# Bipolar_Matrix_Mixer_4x2_v5.net
KiCad netlist of a schematic drawn in EAGLE
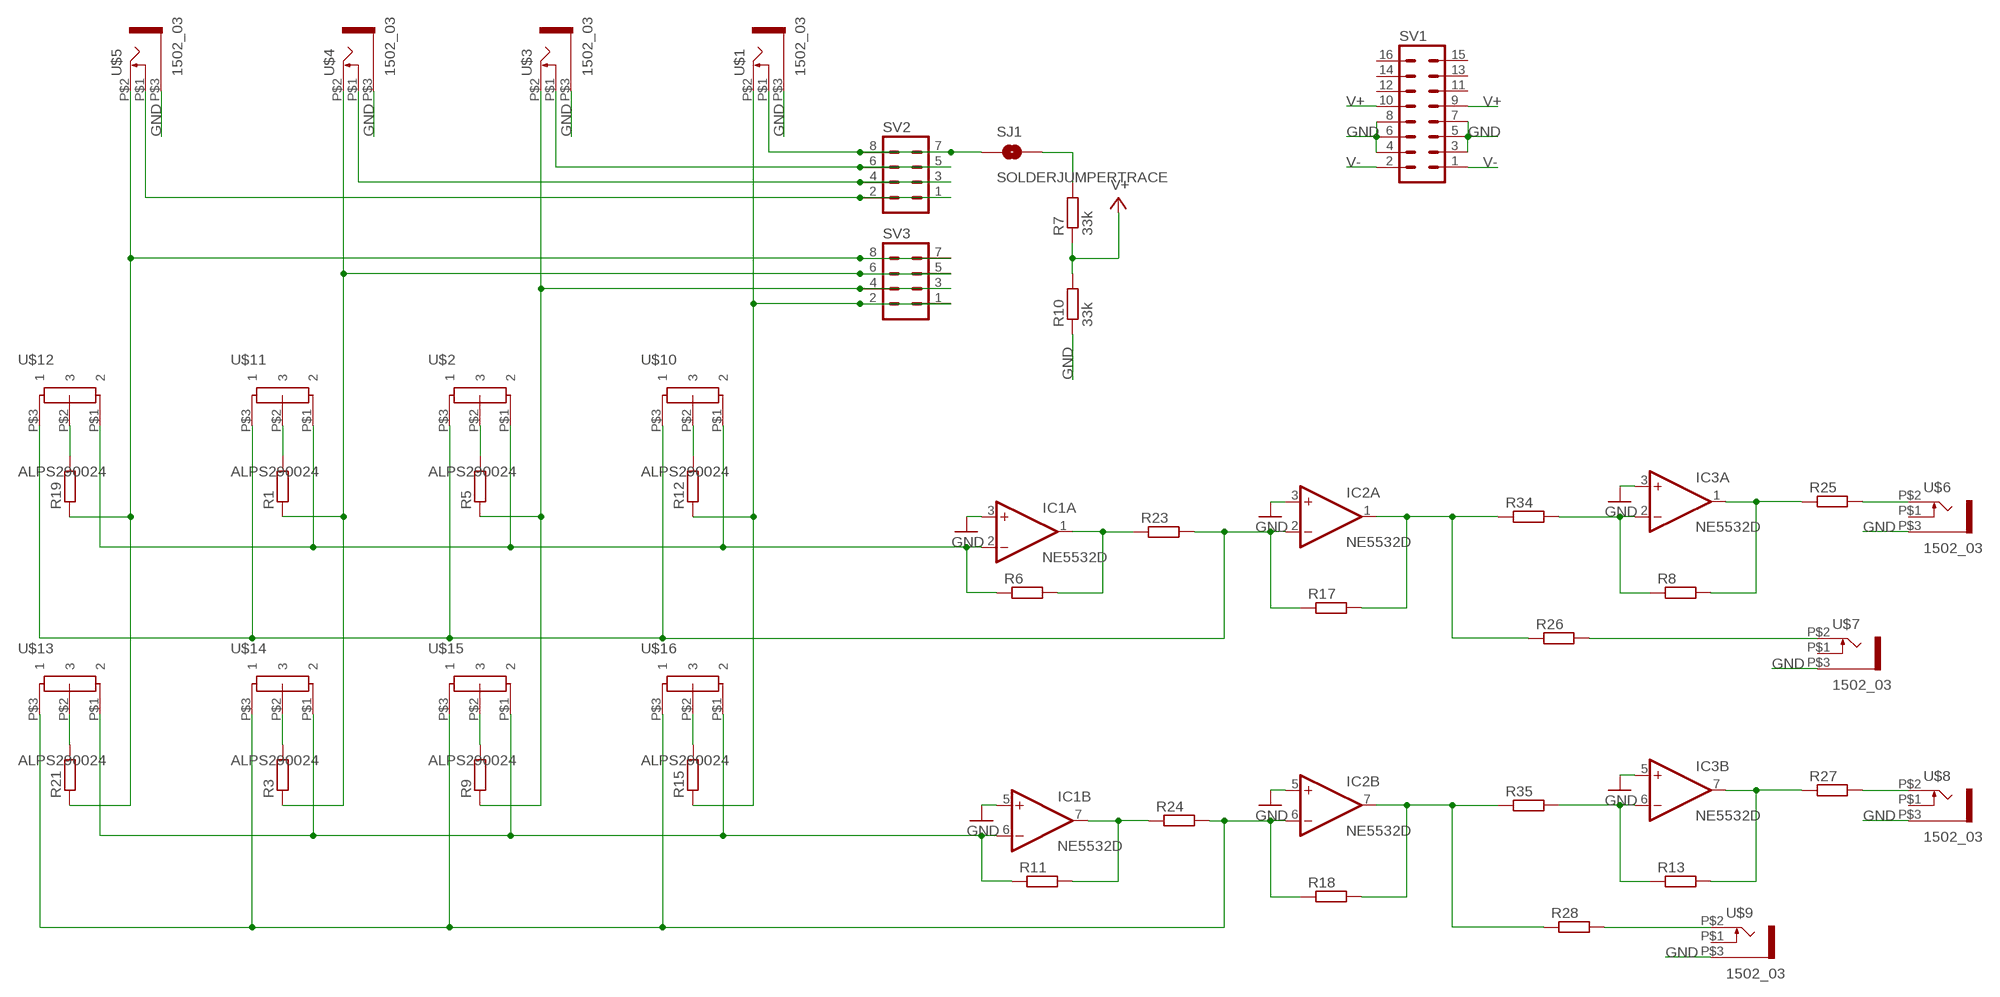
[diagram p0: schematic, sheet 1]

(export (version "E")
  (design (tool "Eeschema 10.0.6"))
  (components
    (comp (ref "IC1")
      (value "NE5532D")
      (footprint "eagle-import:SO08")
      (libsource (lib "eagle-import") (part "NE5532D"))
    )
    (comp (ref "IC2")
      (value "NE5532D")
      (footprint "eagle-import:SO08")
      (libsource (lib "eagle-import") (part "NE5532D"))
    )
    (comp (ref "IC3")
      (value "NE5532D")
      (footprint "eagle-import:SO08")
      (libsource (lib "eagle-import") (part "NE5532D"))
    )
    (comp (ref "R1")
      (value "R-EU_R0603")
      (footprint "eagle-import:R0603")
      (libsource (lib "eagle-import") (part "R-EU_R0603"))
    )
    (comp (ref "R3")
      (value "R-EU_R0603")
      (footprint "eagle-import:R0603")
      (libsource (lib "eagle-import") (part "R-EU_R0603"))
    )
    (comp (ref "R5")
      (value "R-EU_R0603")
      (footprint "eagle-import:R0603")
      (libsource (lib "eagle-import") (part "R-EU_R0603"))
    )
    (comp (ref "R6")
      (value "R-EU_R0603")
      (footprint "eagle-import:R0603")
      (libsource (lib "eagle-import") (part "R-EU_R0603"))
    )
    (comp (ref "R7")
      (value "33k")
      (footprint "eagle-import:R0603")
      (libsource (lib "eagle-import") (part "R-EU_R0603"))
    )
    (comp (ref "R8")
      (value "R-EU_R0603")
      (footprint "eagle-import:R0603")
      (libsource (lib "eagle-import") (part "R-EU_R0603"))
    )
    (comp (ref "R9")
      (value "R-EU_R0603")
      (footprint "eagle-import:R0603")
      (libsource (lib "eagle-import") (part "R-EU_R0603"))
    )
    (comp (ref "R10")
      (value "33k")
      (footprint "eagle-import:R0603")
      (libsource (lib "eagle-import") (part "R-EU_R0603"))
    )
    (comp (ref "R11")
      (value "R-EU_R0603")
      (footprint "eagle-import:R0603")
      (libsource (lib "eagle-import") (part "R-EU_R0603"))
    )
    (comp (ref "R12")
      (value "R-EU_R0603")
      (footprint "eagle-import:R0603")
      (libsource (lib "eagle-import") (part "R-EU_R0603"))
    )
    (comp (ref "R13")
      (value "R-EU_R0603")
      (footprint "eagle-import:R0603")
      (libsource (lib "eagle-import") (part "R-EU_R0603"))
    )
    (comp (ref "R15")
      (value "R-EU_R0603")
      (footprint "eagle-import:R0603")
      (libsource (lib "eagle-import") (part "R-EU_R0603"))
    )
    (comp (ref "R17")
      (value "R-EU_R0603")
      (footprint "eagle-import:R0603")
      (libsource (lib "eagle-import") (part "R-EU_R0603"))
    )
    (comp (ref "R18")
      (value "R-EU_R0603")
      (footprint "eagle-import:R0603")
      (libsource (lib "eagle-import") (part "R-EU_R0603"))
    )
    (comp (ref "R19")
      (value "R-EU_R0603")
      (footprint "eagle-import:R0603")
      (libsource (lib "eagle-import") (part "R-EU_R0603"))
    )
    (comp (ref "R21")
      (value "R-EU_R0603")
      (footprint "eagle-import:R0603")
      (libsource (lib "eagle-import") (part "R-EU_R0603"))
    )
    (comp (ref "R23")
      (value "R-EU_R0603")
      (footprint "eagle-import:R0603")
      (libsource (lib "eagle-import") (part "R-EU_R0603"))
    )
    (comp (ref "R24")
      (value "R-EU_R0603")
      (footprint "eagle-import:R0603")
      (libsource (lib "eagle-import") (part "R-EU_R0603"))
    )
    (comp (ref "R25")
      (value "R-EU_R0603")
      (footprint "eagle-import:R0603")
      (libsource (lib "eagle-import") (part "R-EU_R0603"))
    )
    (comp (ref "R26")
      (value "R-EU_R0603")
      (footprint "eagle-import:R0603")
      (libsource (lib "eagle-import") (part "R-EU_R0603"))
    )
    (comp (ref "R27")
      (value "R-EU_R0603")
      (footprint "eagle-import:R0603")
      (libsource (lib "eagle-import") (part "R-EU_R0603"))
    )
    (comp (ref "R28")
      (value "R-EU_R0603")
      (footprint "eagle-import:R0603")
      (libsource (lib "eagle-import") (part "R-EU_R0603"))
    )
    (comp (ref "R34")
      (value "R-EU_R0603")
      (footprint "eagle-import:R0603")
      (libsource (lib "eagle-import") (part "R-EU_R0603"))
    )
    (comp (ref "R35")
      (value "R-EU_R0603")
      (footprint "eagle-import:R0603")
      (libsource (lib "eagle-import") (part "R-EU_R0603"))
    )
    (comp (ref "SJ1")
      (value "SOLDERJUMPERTRACE")
      (footprint "eagle-import:SJ_2S-TRACE")
      (libsource (lib "eagle-import") (part "SOLDERJUMPERTRACE"))
    )
    (comp (ref "SV1")
      (value "MA08-2")
      (footprint "eagle-import:MA08-2")
      (libsource (lib "eagle-import") (part "MA08-2"))
    )
    (comp (ref "SV2")
      (value "MA04-2")
      (footprint "eagle-import:MA04-2")
      (libsource (lib "eagle-import") (part "MA04-2"))
    )
    (comp (ref "SV3")
      (value "MA04-2")
      (footprint "eagle-import:MA04-2")
      (libsource (lib "eagle-import") (part "MA04-2"))
    )
    (comp (ref "U$1")
      (value "1502_03")
      (footprint "eagle-import:1502_03")
      (libsource (lib "eagle-import") (part "1502_03"))
    )
    (comp (ref "U$2")
      (value "ALPS290024")
      (footprint "eagle-import:POT")
      (libsource (lib "eagle-import") (part "ALPS290024"))
    )
    (comp (ref "U$3")
      (value "1502_03")
      (footprint "eagle-import:1502_03")
      (libsource (lib "eagle-import") (part "1502_03"))
    )
    (comp (ref "U$4")
      (value "1502_03")
      (footprint "eagle-import:1502_03")
      (libsource (lib "eagle-import") (part "1502_03"))
    )
    (comp (ref "U$5")
      (value "1502_03")
      (footprint "eagle-import:1502_03")
      (libsource (lib "eagle-import") (part "1502_03"))
    )
    (comp (ref "U$6")
      (value "1502_03")
      (footprint "eagle-import:1502_03")
      (libsource (lib "eagle-import") (part "1502_03"))
    )
    (comp (ref "U$7")
      (value "1502_03")
      (footprint "eagle-import:1502_03")
      (libsource (lib "eagle-import") (part "1502_03"))
    )
    (comp (ref "U$8")
      (value "1502_03")
      (footprint "eagle-import:1502_03")
      (libsource (lib "eagle-import") (part "1502_03"))
    )
    (comp (ref "U$9")
      (value "1502_03")
      (footprint "eagle-import:1502_03")
      (libsource (lib "eagle-import") (part "1502_03"))
    )
    (comp (ref "U$10")
      (value "ALPS290024")
      (footprint "eagle-import:POT")
      (libsource (lib "eagle-import") (part "ALPS290024"))
    )
    (comp (ref "U$11")
      (value "ALPS290024")
      (footprint "eagle-import:POT")
      (libsource (lib "eagle-import") (part "ALPS290024"))
    )
    (comp (ref "U$12")
      (value "ALPS290024")
      (footprint "eagle-import:POT")
      (libsource (lib "eagle-import") (part "ALPS290024"))
    )
    (comp (ref "U$13")
      (value "ALPS290024")
      (footprint "eagle-import:POT")
      (libsource (lib "eagle-import") (part "ALPS290024"))
    )
    (comp (ref "U$14")
      (value "ALPS290024")
      (footprint "eagle-import:POT")
      (libsource (lib "eagle-import") (part "ALPS290024"))
    )
    (comp (ref "U$15")
      (value "ALPS290024")
      (footprint "eagle-import:POT")
      (libsource (lib "eagle-import") (part "ALPS290024"))
    )
    (comp (ref "U$16")
      (value "ALPS290024")
      (footprint "eagle-import:POT")
      (libsource (lib "eagle-import") (part "ALPS290024"))
    )
  )
  (nets
    (net (code "1") (name "/V-") (class "Default")
      (node (ref "SV1") (pin "1") (pinfunction "1_1") (pintype "passive"))
      (node (ref "SV1") (pin "2") (pinfunction "2_2") (pintype "passive"))
    )
    (net (code "2") (name "GND") (class "Default")
      (node (ref "IC1") (pin "3") (pinfunction "+IN_3") (pintype "input"))
      (node (ref "IC1") (pin "5") (pinfunction "+IN_5") (pintype "input"))
      (node (ref "IC2") (pin "3") (pinfunction "+IN_3") (pintype "input"))
      (node (ref "IC2") (pin "5") (pinfunction "+IN_5") (pintype "input"))
      (node (ref "IC3") (pin "3") (pinfunction "+IN_3") (pintype "input"))
      (node (ref "IC3") (pin "5") (pinfunction "+IN_5") (pintype "input"))
      (node (ref "R10") (pin "1") (pinfunction "1_1") (pintype "passive"))
      (node (ref "SV1") (pin "3") (pinfunction "3_3") (pintype "passive"))
      (node (ref "SV1") (pin "4") (pinfunction "4_4") (pintype "passive"))
      (node (ref "SV1") (pin "5") (pinfunction "5_5") (pintype "passive"))
      (node (ref "SV1") (pin "6") (pinfunction "6_6") (pintype "passive"))
      (node (ref "SV1") (pin "7") (pinfunction "7_7") (pintype "passive"))
      (node (ref "SV1") (pin "8") (pinfunction "8_8") (pintype "passive"))
      (node (ref "U$1") (pin "P$3") (pinfunction "5_P$3") (pintype "passive"))
      (node (ref "U$3") (pin "P$3") (pinfunction "5_P$3") (pintype "passive"))
      (node (ref "U$4") (pin "P$3") (pinfunction "5_P$3") (pintype "passive"))
      (node (ref "U$5") (pin "P$3") (pinfunction "5_P$3") (pintype "passive"))
      (node (ref "U$6") (pin "P$3") (pinfunction "5_P$3") (pintype "passive"))
      (node (ref "U$7") (pin "P$3") (pinfunction "5_P$3") (pintype "passive"))
      (node (ref "U$8") (pin "P$3") (pinfunction "5_P$3") (pintype "passive"))
      (node (ref "U$9") (pin "P$3") (pinfunction "5_P$3") (pintype "passive"))
    )
    (net (code "3") (name "Net-(IC1A--IN)") (class "Default")
      (node (ref "IC1") (pin "2") (pinfunction "-IN_2") (pintype "input"))
      (node (ref "R6") (pin "1") (pinfunction "1_1") (pintype "passive"))
      (node (ref "U$10") (pin "P$1") (pinfunction "2_P$1") (pintype "bidirectional"))
      (node (ref "U$11") (pin "P$1") (pinfunction "2_P$1") (pintype "bidirectional"))
      (node (ref "U$12") (pin "P$1") (pinfunction "2_P$1") (pintype "bidirectional"))
      (node (ref "U$2") (pin "P$1") (pinfunction "2_P$1") (pintype "bidirectional"))
    )
    (net (code "4") (name "Net-(IC1A-OUT)") (class "Default")
      (node (ref "IC1") (pin "1") (pinfunction "OUT_1") (pintype "output"))
      (node (ref "R23") (pin "1") (pinfunction "1_1") (pintype "passive"))
      (node (ref "R6") (pin "2") (pinfunction "2_2") (pintype "passive"))
    )
    (net (code "5") (name "Net-(IC1B--IN)") (class "Default")
      (node (ref "IC1") (pin "6") (pinfunction "-IN_6") (pintype "input"))
      (node (ref "R11") (pin "1") (pinfunction "1_1") (pintype "passive"))
      (node (ref "U$13") (pin "P$1") (pinfunction "2_P$1") (pintype "bidirectional"))
      (node (ref "U$14") (pin "P$1") (pinfunction "2_P$1") (pintype "bidirectional"))
      (node (ref "U$15") (pin "P$1") (pinfunction "2_P$1") (pintype "bidirectional"))
      (node (ref "U$16") (pin "P$1") (pinfunction "2_P$1") (pintype "bidirectional"))
    )
    (net (code "6") (name "Net-(IC1B-OUT)") (class "Default")
      (node (ref "IC1") (pin "7") (pinfunction "OUT_7") (pintype "output"))
      (node (ref "R11") (pin "2") (pinfunction "2_2") (pintype "passive"))
      (node (ref "R24") (pin "1") (pinfunction "1_1") (pintype "passive"))
    )
    (net (code "7") (name "Net-(IC2A--IN)") (class "Default")
      (node (ref "IC2") (pin "2") (pinfunction "-IN_2") (pintype "input"))
      (node (ref "R17") (pin "1") (pinfunction "1_1") (pintype "passive"))
      (node (ref "R23") (pin "2") (pinfunction "2_2") (pintype "passive"))
      (node (ref "U$10") (pin "P$3") (pinfunction "1_P$3") (pintype "bidirectional"))
      (node (ref "U$11") (pin "P$3") (pinfunction "1_P$3") (pintype "bidirectional"))
      (node (ref "U$12") (pin "P$3") (pinfunction "1_P$3") (pintype "bidirectional"))
      (node (ref "U$2") (pin "P$3") (pinfunction "1_P$3") (pintype "bidirectional"))
    )
    (net (code "8") (name "Net-(IC2A-OUT)") (class "Default")
      (node (ref "IC2") (pin "1") (pinfunction "OUT_1") (pintype "output"))
      (node (ref "R17") (pin "2") (pinfunction "2_2") (pintype "passive"))
      (node (ref "R26") (pin "1") (pinfunction "1_1") (pintype "passive"))
      (node (ref "R34") (pin "1") (pinfunction "1_1") (pintype "passive"))
    )
    (net (code "9") (name "Net-(IC2B--IN)") (class "Default")
      (node (ref "IC2") (pin "6") (pinfunction "-IN_6") (pintype "input"))
      (node (ref "R18") (pin "1") (pinfunction "1_1") (pintype "passive"))
      (node (ref "R24") (pin "2") (pinfunction "2_2") (pintype "passive"))
      (node (ref "U$13") (pin "P$3") (pinfunction "1_P$3") (pintype "bidirectional"))
      (node (ref "U$14") (pin "P$3") (pinfunction "1_P$3") (pintype "bidirectional"))
      (node (ref "U$15") (pin "P$3") (pinfunction "1_P$3") (pintype "bidirectional"))
      (node (ref "U$16") (pin "P$3") (pinfunction "1_P$3") (pintype "bidirectional"))
    )
    (net (code "10") (name "Net-(IC2B-OUT)") (class "Default")
      (node (ref "IC2") (pin "7") (pinfunction "OUT_7") (pintype "output"))
      (node (ref "R18") (pin "2") (pinfunction "2_2") (pintype "passive"))
      (node (ref "R28") (pin "1") (pinfunction "1_1") (pintype "passive"))
      (node (ref "R35") (pin "1") (pinfunction "1_1") (pintype "passive"))
    )
    (net (code "11") (name "Net-(IC3A--IN)") (class "Default")
      (node (ref "IC3") (pin "2") (pinfunction "-IN_2") (pintype "input"))
      (node (ref "R34") (pin "2") (pinfunction "2_2") (pintype "passive"))
      (node (ref "R8") (pin "1") (pinfunction "1_1") (pintype "passive"))
    )
    (net (code "12") (name "Net-(IC3A-OUT)") (class "Default")
      (node (ref "IC3") (pin "1") (pinfunction "OUT_1") (pintype "output"))
      (node (ref "R25") (pin "1") (pinfunction "1_1") (pintype "passive"))
      (node (ref "R8") (pin "2") (pinfunction "2_2") (pintype "passive"))
    )
    (net (code "13") (name "Net-(IC3B--IN)") (class "Default")
      (node (ref "IC3") (pin "6") (pinfunction "-IN_6") (pintype "input"))
      (node (ref "R13") (pin "1") (pinfunction "1_1") (pintype "passive"))
      (node (ref "R35") (pin "2") (pinfunction "2_2") (pintype "passive"))
    )
    (net (code "14") (name "Net-(IC3B-OUT)") (class "Default")
      (node (ref "IC3") (pin "7") (pinfunction "OUT_7") (pintype "output"))
      (node (ref "R13") (pin "2") (pinfunction "2_2") (pintype "passive"))
      (node (ref "R27") (pin "1") (pinfunction "1_1") (pintype "passive"))
    )
    (net (code "15") (name "Net-(R7-Pad2)") (class "Default")
      (node (ref "R7") (pin "2") (pinfunction "2_2") (pintype "passive"))
      (node (ref "SJ1") (pin "2") (pinfunction "2_2") (pintype "passive"))
    )
    (net (code "16") (name "Net-(U$1-3)") (class "Default")
      (node (ref "R12") (pin "1") (pinfunction "1_1") (pintype "passive"))
      (node (ref "R15") (pin "1") (pinfunction "1_1") (pintype "passive"))
      (node (ref "SV3") (pin "1") (pinfunction "1_1") (pintype "passive"))
      (node (ref "SV3") (pin "2") (pinfunction "2_2") (pintype "passive"))
      (node (ref "U$1") (pin "P$2") (pinfunction "3_P$2") (pintype "passive"))
    )
    (net (code "17") (name "Net-(U$1-4)") (class "Default")
      (node (ref "SJ1") (pin "1") (pinfunction "1_1") (pintype "passive"))
      (node (ref "SV2") (pin "7") (pinfunction "7_7") (pintype "passive"))
      (node (ref "SV2") (pin "8") (pinfunction "8_8") (pintype "passive"))
      (node (ref "U$1") (pin "P$1") (pinfunction "4_P$1") (pintype "passive"))
    )
    (net (code "18") (name "Net-(U$2-3)") (class "Default")
      (node (ref "R5") (pin "2") (pinfunction "2_2") (pintype "passive"))
      (node (ref "U$2") (pin "P$2") (pinfunction "3_P$2") (pintype "bidirectional"))
    )
    (net (code "19") (name "Net-(U$3-3)") (class "Default")
      (node (ref "R5") (pin "1") (pinfunction "1_1") (pintype "passive"))
      (node (ref "R9") (pin "1") (pinfunction "1_1") (pintype "passive"))
      (node (ref "SV3") (pin "3") (pinfunction "3_3") (pintype "passive"))
      (node (ref "SV3") (pin "4") (pinfunction "4_4") (pintype "passive"))
      (node (ref "U$3") (pin "P$2") (pinfunction "3_P$2") (pintype "passive"))
    )
    (net (code "20") (name "Net-(U$3-4)") (class "Default")
      (node (ref "SV2") (pin "5") (pinfunction "5_5") (pintype "passive"))
      (node (ref "SV2") (pin "6") (pinfunction "6_6") (pintype "passive"))
      (node (ref "U$3") (pin "P$1") (pinfunction "4_P$1") (pintype "passive"))
    )
    (net (code "21") (name "Net-(U$4-3)") (class "Default")
      (node (ref "R1") (pin "1") (pinfunction "1_1") (pintype "passive"))
      (node (ref "R3") (pin "1") (pinfunction "1_1") (pintype "passive"))
      (node (ref "SV3") (pin "5") (pinfunction "5_5") (pintype "passive"))
      (node (ref "SV3") (pin "6") (pinfunction "6_6") (pintype "passive"))
      (node (ref "U$4") (pin "P$2") (pinfunction "3_P$2") (pintype "passive"))
    )
    (net (code "22") (name "Net-(U$4-4)") (class "Default")
      (node (ref "SV2") (pin "3") (pinfunction "3_3") (pintype "passive"))
      (node (ref "SV2") (pin "4") (pinfunction "4_4") (pintype "passive"))
      (node (ref "U$4") (pin "P$1") (pinfunction "4_P$1") (pintype "passive"))
    )
    (net (code "23") (name "Net-(U$5-3)") (class "Default")
      (node (ref "R19") (pin "1") (pinfunction "1_1") (pintype "passive"))
      (node (ref "R21") (pin "1") (pinfunction "1_1") (pintype "passive"))
      (node (ref "SV3") (pin "7") (pinfunction "7_7") (pintype "passive"))
      (node (ref "SV3") (pin "8") (pinfunction "8_8") (pintype "passive"))
      (node (ref "U$5") (pin "P$2") (pinfunction "3_P$2") (pintype "passive"))
    )
    (net (code "24") (name "Net-(U$5-4)") (class "Default")
      (node (ref "SV2") (pin "1") (pinfunction "1_1") (pintype "passive"))
      (node (ref "SV2") (pin "2") (pinfunction "2_2") (pintype "passive"))
      (node (ref "U$5") (pin "P$1") (pinfunction "4_P$1") (pintype "passive"))
    )
    (net (code "25") (name "Net-(U$6-3)") (class "Default")
      (node (ref "R25") (pin "2") (pinfunction "2_2") (pintype "passive"))
      (node (ref "U$6") (pin "P$2") (pinfunction "3_P$2") (pintype "passive"))
    )
    (net (code "26") (name "Net-(U$7-3)") (class "Default")
      (node (ref "R26") (pin "2") (pinfunction "2_2") (pintype "passive"))
      (node (ref "U$7") (pin "P$2") (pinfunction "3_P$2") (pintype "passive"))
    )
    (net (code "27") (name "Net-(U$8-3)") (class "Default")
      (node (ref "R27") (pin "2") (pinfunction "2_2") (pintype "passive"))
      (node (ref "U$8") (pin "P$2") (pinfunction "3_P$2") (pintype "passive"))
    )
    (net (code "28") (name "Net-(U$9-3)") (class "Default")
      (node (ref "R28") (pin "2") (pinfunction "2_2") (pintype "passive"))
      (node (ref "U$9") (pin "P$2") (pinfunction "3_P$2") (pintype "passive"))
    )
    (net (code "29") (name "Net-(U$10-3)") (class "Default")
      (node (ref "R12") (pin "2") (pinfunction "2_2") (pintype "passive"))
      (node (ref "U$10") (pin "P$2") (pinfunction "3_P$2") (pintype "bidirectional"))
    )
    (net (code "30") (name "Net-(U$11-3)") (class "Default")
      (node (ref "R1") (pin "2") (pinfunction "2_2") (pintype "passive"))
      (node (ref "U$11") (pin "P$2") (pinfunction "3_P$2") (pintype "bidirectional"))
    )
    (net (code "31") (name "Net-(U$12-3)") (class "Default")
      (node (ref "R19") (pin "2") (pinfunction "2_2") (pintype "passive"))
      (node (ref "U$12") (pin "P$2") (pinfunction "3_P$2") (pintype "bidirectional"))
    )
    (net (code "32") (name "Net-(U$13-3)") (class "Default")
      (node (ref "R21") (pin "2") (pinfunction "2_2") (pintype "passive"))
      (node (ref "U$13") (pin "P$2") (pinfunction "3_P$2") (pintype "bidirectional"))
    )
    (net (code "33") (name "Net-(U$14-3)") (class "Default")
      (node (ref "R3") (pin "2") (pinfunction "2_2") (pintype "passive"))
      (node (ref "U$14") (pin "P$2") (pinfunction "3_P$2") (pintype "bidirectional"))
    )
    (net (code "34") (name "Net-(U$15-3)") (class "Default")
      (node (ref "R9") (pin "2") (pinfunction "2_2") (pintype "passive"))
      (node (ref "U$15") (pin "P$2") (pinfunction "3_P$2") (pintype "bidirectional"))
    )
    (net (code "35") (name "Net-(U$16-3)") (class "Default")
      (node (ref "R15") (pin "2") (pinfunction "2_2") (pintype "passive"))
      (node (ref "U$16") (pin "P$2") (pinfunction "3_P$2") (pintype "bidirectional"))
    )
    (net (code "36") (name "V+") (class "Default")
      (node (ref "R10") (pin "2") (pinfunction "2_2") (pintype "passive"))
      (node (ref "R7") (pin "1") (pinfunction "1_1") (pintype "passive"))
      (node (ref "SV1") (pin "10") (pinfunction "10_10") (pintype "passive"))
      (node (ref "SV1") (pin "9") (pinfunction "9_9") (pintype "passive"))
    )
    (net (code "37") (name "unconnected-(SV1-Pad11)") (class "Default")
      (node (ref "SV1") (pin "11") (pinfunction "11_11") (pintype "passive"))
    )
    (net (code "38") (name "unconnected-(SV1-Pad12)") (class "Default")
      (node (ref "SV1") (pin "12") (pinfunction "12_12") (pintype "passive"))
    )
    (net (code "39") (name "unconnected-(SV1-Pad13)") (class "Default")
      (node (ref "SV1") (pin "13") (pinfunction "13_13") (pintype "passive"))
    )
    (net (code "40") (name "unconnected-(SV1-Pad14)") (class "Default")
      (node (ref "SV1") (pin "14") (pinfunction "14_14") (pintype "passive"))
    )
    (net (code "41") (name "unconnected-(SV1-Pad15)") (class "Default")
      (node (ref "SV1") (pin "15") (pinfunction "15_15") (pintype "passive"))
    )
    (net (code "42") (name "unconnected-(SV1-Pad16)") (class "Default")
      (node (ref "SV1") (pin "16") (pinfunction "16_16") (pintype "passive"))
    )
    (net (code "43") (name "unconnected-(U$6-4-PadP$1)") (class "Default")
      (node (ref "U$6") (pin "P$1") (pinfunction "4_P$1") (pintype "passive"))
    )
    (net (code "44") (name "unconnected-(U$7-4-PadP$1)") (class "Default")
      (node (ref "U$7") (pin "P$1") (pinfunction "4_P$1") (pintype "passive"))
    )
    (net (code "45") (name "unconnected-(U$8-4-PadP$1)") (class "Default")
      (node (ref "U$8") (pin "P$1") (pinfunction "4_P$1") (pintype "passive"))
    )
    (net (code "46") (name "unconnected-(U$9-4-PadP$1)") (class "Default")
      (node (ref "U$9") (pin "P$1") (pinfunction "4_P$1") (pintype "passive"))
    )
  )
)
